# Board.net
KiCad netlist of a schematic drawn in EAGLE
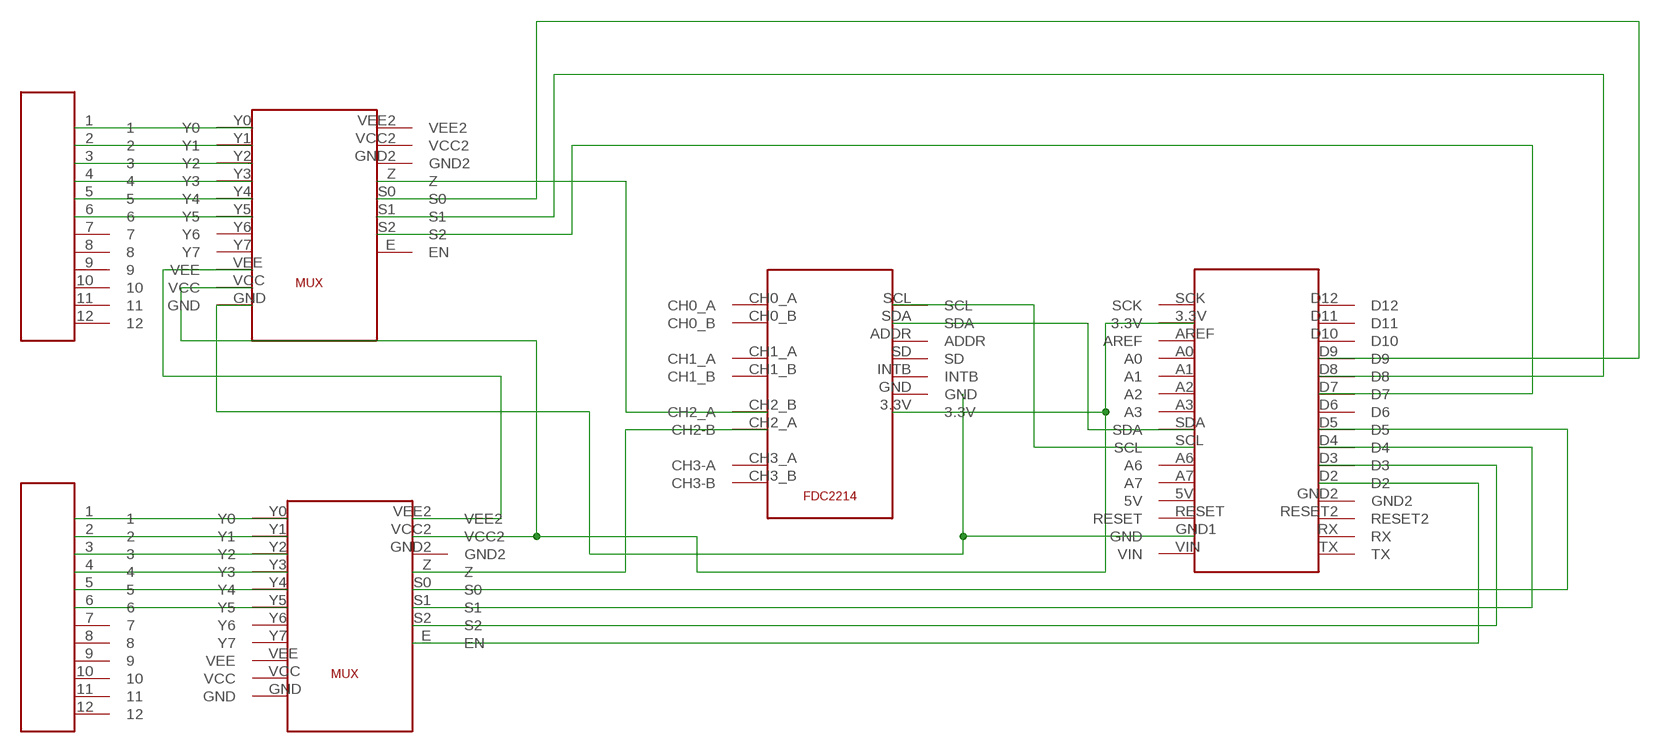
[diagram p0: schematic, sheet 1]

(export (version "E")
  (design (tool "Eeschema 10.0.6"))
  (components
    (comp (ref "U$1")
      (value "BLE33BLE33")
      (footprint "eagle-import:BLE33")
      (libsource (lib "eagle-import") (part "BLE33BLE33"))
    )
    (comp (ref "U$2")
      (value "MUXMUX")
      (footprint "eagle-import:MUX")
      (libsource (lib "eagle-import") (part "MUXMUX"))
    )
    (comp (ref "U$3")
      (value "MUXMUX")
      (footprint "eagle-import:MUX")
      (libsource (lib "eagle-import") (part "MUXMUX"))
    )
    (comp (ref "U$4")
      (value "MOLEXMOLEX")
      (footprint "eagle-import:MOLEX")
      (libsource (lib "eagle-import") (part "MOLEXMOLEX"))
    )
    (comp (ref "U$5")
      (value "MOLEXMOLEX")
      (footprint "eagle-import:MOLEX")
      (libsource (lib "eagle-import") (part "MOLEXMOLEX"))
    )
    (comp (ref "U$6")
      (value "FDC2214FDC2214")
      (footprint "eagle-import:FDC2214")
      (libsource (lib "eagle-import") (part "FDC2214FDC2214"))
    )
  )
  (nets
    (net (code "1") (name "Net-(U$1-GND)") (class "Default")
      (node (ref "U$1") (pin "GND1") (pinfunction "GND_GND1") (pintype "bidirectional"))
      (node (ref "U$2") (pin "GND") (pinfunction "GND_GND") (pintype "bidirectional"))
    )
    (net (code "2") (name "Net-(U$1-Pad3.3V)") (class "Default")
      (node (ref "U$1") (pin "3.3V") (pinfunction "3.3V_3.3V") (pintype "bidirectional"))
      (node (ref "U$2") (pin "VCC") (pinfunction "VCC_VCC") (pintype "bidirectional"))
      (node (ref "U$3") (pin "VCC2") (pinfunction "VCC2_VCC2") (pintype "bidirectional"))
      (node (ref "U$6") (pin "3.3V") (pinfunction "3.3V_3.3V") (pintype "bidirectional"))
    )
    (net (code "3") (name "Net-(U$1-PadD3)") (class "Default")
      (node (ref "U$1") (pin "D3") (pinfunction "D3_D3") (pintype "bidirectional"))
      (node (ref "U$3") (pin "S2") (pinfunction "S2_S2") (pintype "bidirectional"))
    )
    (net (code "4") (name "Net-(U$1-PadD4)") (class "Default")
      (node (ref "U$1") (pin "D4") (pinfunction "D4_D4") (pintype "bidirectional"))
      (node (ref "U$3") (pin "S1") (pinfunction "S1_S1") (pintype "bidirectional"))
    )
    (net (code "5") (name "Net-(U$1-PadD5)") (class "Default")
      (node (ref "U$1") (pin "D5") (pinfunction "D5_D5") (pintype "bidirectional"))
      (node (ref "U$3") (pin "S0") (pinfunction "S0_S0") (pintype "bidirectional"))
    )
    (net (code "6") (name "Net-(U$1-PadD7)") (class "Default")
      (node (ref "U$1") (pin "D7") (pinfunction "D7_D7") (pintype "bidirectional"))
      (node (ref "U$2") (pin "S2") (pinfunction "S2_S2") (pintype "bidirectional"))
    )
    (net (code "7") (name "Net-(U$1-PadD8)") (class "Default")
      (node (ref "U$1") (pin "D8") (pinfunction "D8_D8") (pintype "bidirectional"))
      (node (ref "U$2") (pin "S1") (pinfunction "S1_S1") (pintype "bidirectional"))
    )
    (net (code "8") (name "Net-(U$1-PadD9)") (class "Default")
      (node (ref "U$1") (pin "D9") (pinfunction "D9_D9") (pintype "bidirectional"))
      (node (ref "U$2") (pin "S0") (pinfunction "S0_S0") (pintype "bidirectional"))
    )
    (net (code "9") (name "Net-(U$1-PadSCL)") (class "Default")
      (node (ref "U$1") (pin "SCL") (pinfunction "SCL_SCL") (pintype "bidirectional"))
      (node (ref "U$6") (pin "SCL") (pinfunction "SCL_SCL") (pintype "bidirectional"))
    )
    (net (code "10") (name "Net-(U$1-PadSDA)") (class "Default")
      (node (ref "U$1") (pin "SDA") (pinfunction "SDA_SDA") (pintype "bidirectional"))
      (node (ref "U$6") (pin "SDA") (pinfunction "SDA_SDA") (pintype "bidirectional"))
    )
    (net (code "11") (name "Net-(U$2-PadVEE)") (class "Default")
      (node (ref "U$2") (pin "VEE") (pinfunction "VEE_VEE") (pintype "bidirectional"))
      (node (ref "U$3") (pin "VEE2") (pinfunction "VEE2_VEE2") (pintype "bidirectional"))
    )
    (net (code "12") (name "Net-(U$2-PadY0)") (class "Default")
      (node (ref "U$2") (pin "Y0") (pinfunction "Y0_Y0") (pintype "bidirectional"))
      (node (ref "U$4") (pin "1") (pinfunction "1_1") (pintype "bidirectional"))
    )
    (net (code "13") (name "Net-(U$2-PadY1)") (class "Default")
      (node (ref "U$2") (pin "Y1") (pinfunction "Y1_Y1") (pintype "bidirectional"))
      (node (ref "U$4") (pin "2") (pinfunction "2_2") (pintype "bidirectional"))
    )
    (net (code "14") (name "Net-(U$2-PadY2)") (class "Default")
      (node (ref "U$2") (pin "Y2") (pinfunction "Y2_Y2") (pintype "bidirectional"))
      (node (ref "U$4") (pin "3") (pinfunction "3_3") (pintype "bidirectional"))
    )
    (net (code "15") (name "Net-(U$2-PadY3)") (class "Default")
      (node (ref "U$2") (pin "Y3") (pinfunction "Y3_Y3") (pintype "bidirectional"))
      (node (ref "U$4") (pin "4") (pinfunction "4_4") (pintype "bidirectional"))
    )
    (net (code "16") (name "Net-(U$2-PadY4)") (class "Default")
      (node (ref "U$2") (pin "Y4") (pinfunction "Y4_Y4") (pintype "bidirectional"))
      (node (ref "U$4") (pin "5") (pinfunction "5_5") (pintype "bidirectional"))
    )
    (net (code "17") (name "Net-(U$2-PadY5)") (class "Default")
      (node (ref "U$2") (pin "Y5") (pinfunction "Y5_Y5") (pintype "bidirectional"))
      (node (ref "U$4") (pin "6") (pinfunction "6_6") (pintype "bidirectional"))
    )
    (net (code "18") (name "Net-(U$3-EN)") (class "Default")
      (node (ref "U$1") (pin "D2") (pinfunction "D2_D2") (pintype "bidirectional"))
      (node (ref "U$3") (pin "E") (pinfunction "EN_E") (pintype "bidirectional"))
    )
    (net (code "19") (name "Net-(U$3-PadY0)") (class "Default")
      (node (ref "U$3") (pin "Y0") (pinfunction "Y0_Y0") (pintype "bidirectional"))
      (node (ref "U$5") (pin "1") (pinfunction "1_1") (pintype "bidirectional"))
    )
    (net (code "20") (name "Net-(U$3-PadY1)") (class "Default")
      (node (ref "U$3") (pin "Y1") (pinfunction "Y1_Y1") (pintype "bidirectional"))
      (node (ref "U$5") (pin "2") (pinfunction "2_2") (pintype "bidirectional"))
    )
    (net (code "21") (name "Net-(U$3-PadY2)") (class "Default")
      (node (ref "U$3") (pin "Y2") (pinfunction "Y2_Y2") (pintype "bidirectional"))
      (node (ref "U$5") (pin "3") (pinfunction "3_3") (pintype "bidirectional"))
    )
    (net (code "22") (name "Net-(U$3-PadY3)") (class "Default")
      (node (ref "U$3") (pin "Y3") (pinfunction "Y3_Y3") (pintype "bidirectional"))
      (node (ref "U$5") (pin "4") (pinfunction "4_4") (pintype "bidirectional"))
    )
    (net (code "23") (name "Net-(U$3-PadY4)") (class "Default")
      (node (ref "U$3") (pin "Y4") (pinfunction "Y4_Y4") (pintype "bidirectional"))
      (node (ref "U$5") (pin "5") (pinfunction "5_5") (pintype "bidirectional"))
    )
    (net (code "24") (name "Net-(U$3-PadY5)") (class "Default")
      (node (ref "U$3") (pin "Y5") (pinfunction "Y5_Y5") (pintype "bidirectional"))
      (node (ref "U$5") (pin "6") (pinfunction "6_6") (pintype "bidirectional"))
    )
    (net (code "25") (name "Net-(U$6-CH2-B)") (class "Default")
      (node (ref "U$3") (pin "Z") (pinfunction "Z_Z") (pintype "bidirectional"))
      (node (ref "U$6") (pin "CH2_A") (pinfunction "CH2-B_CH2_A") (pintype "bidirectional"))
    )
    (net (code "26") (name "Net-(U$6-CH2_A)") (class "Default")
      (node (ref "U$2") (pin "Z") (pinfunction "Z_Z") (pintype "bidirectional"))
      (node (ref "U$6") (pin "CH2_B") (pinfunction "CH2_A_CH2_B") (pintype "bidirectional"))
    )
    (net (code "27") (name "unconnected-(U$1-Pad5V)") (class "Default")
      (node (ref "U$1") (pin "5V") (pinfunction "5V_5V") (pintype "bidirectional"))
    )
    (net (code "28") (name "unconnected-(U$1-PadA0)") (class "Default")
      (node (ref "U$1") (pin "A0") (pinfunction "A0_A0") (pintype "bidirectional"))
    )
    (net (code "29") (name "unconnected-(U$1-PadA1)") (class "Default")
      (node (ref "U$1") (pin "A1") (pinfunction "A1_A1") (pintype "bidirectional"))
    )
    (net (code "30") (name "unconnected-(U$1-PadA2)") (class "Default")
      (node (ref "U$1") (pin "A2") (pinfunction "A2_A2") (pintype "bidirectional"))
    )
    (net (code "31") (name "unconnected-(U$1-PadA3)") (class "Default")
      (node (ref "U$1") (pin "A3") (pinfunction "A3_A3") (pintype "bidirectional"))
    )
    (net (code "32") (name "unconnected-(U$1-PadA6)") (class "Default")
      (node (ref "U$1") (pin "A6") (pinfunction "A6_A6") (pintype "bidirectional"))
    )
    (net (code "33") (name "unconnected-(U$1-PadA7)") (class "Default")
      (node (ref "U$1") (pin "A7") (pinfunction "A7_A7") (pintype "bidirectional"))
    )
    (net (code "34") (name "unconnected-(U$1-PadAREF)") (class "Default")
      (node (ref "U$1") (pin "AREF") (pinfunction "AREF_AREF") (pintype "bidirectional"))
    )
    (net (code "35") (name "unconnected-(U$1-PadD6)") (class "Default")
      (node (ref "U$1") (pin "D6") (pinfunction "D6_D6") (pintype "bidirectional"))
    )
    (net (code "36") (name "unconnected-(U$1-PadD10)") (class "Default")
      (node (ref "U$1") (pin "D10") (pinfunction "D10_D10") (pintype "bidirectional"))
    )
    (net (code "37") (name "unconnected-(U$1-PadD11)") (class "Default")
      (node (ref "U$1") (pin "D11") (pinfunction "D11_D11") (pintype "bidirectional"))
    )
    (net (code "38") (name "unconnected-(U$1-PadD12)") (class "Default")
      (node (ref "U$1") (pin "D12") (pinfunction "D12_D12") (pintype "bidirectional"))
    )
    (net (code "39") (name "unconnected-(U$1-PadGND2)") (class "Default")
      (node (ref "U$1") (pin "GND2") (pinfunction "GND2_GND2") (pintype "bidirectional"))
    )
    (net (code "40") (name "unconnected-(U$1-PadRESET)") (class "Default")
      (node (ref "U$1") (pin "RESET") (pinfunction "RESET_RESET") (pintype "bidirectional"))
    )
    (net (code "41") (name "unconnected-(U$1-PadRESET2)") (class "Default")
      (node (ref "U$1") (pin "RESET2") (pinfunction "RESET2_RESET2") (pintype "bidirectional"))
    )
    (net (code "42") (name "unconnected-(U$1-PadRX)") (class "Default")
      (node (ref "U$1") (pin "RX") (pinfunction "RX_RX") (pintype "bidirectional"))
    )
    (net (code "43") (name "unconnected-(U$1-PadSCK)") (class "Default")
      (node (ref "U$1") (pin "SCK") (pinfunction "SCK_SCK") (pintype "bidirectional"))
    )
    (net (code "44") (name "unconnected-(U$1-PadTX)") (class "Default")
      (node (ref "U$1") (pin "TX") (pinfunction "TX_TX") (pintype "bidirectional"))
    )
    (net (code "45") (name "unconnected-(U$1-PadVIN)") (class "Default")
      (node (ref "U$1") (pin "VIN") (pinfunction "VIN_VIN") (pintype "bidirectional"))
    )
    (net (code "46") (name "unconnected-(U$2-EN-PadE)") (class "Default")
      (node (ref "U$2") (pin "E") (pinfunction "EN_E") (pintype "bidirectional"))
    )
    (net (code "47") (name "unconnected-(U$2-PadGND2)") (class "Default")
      (node (ref "U$2") (pin "GND2") (pinfunction "GND2_GND2") (pintype "bidirectional"))
    )
    (net (code "48") (name "unconnected-(U$2-PadVCC2)") (class "Default")
      (node (ref "U$2") (pin "VCC2") (pinfunction "VCC2_VCC2") (pintype "bidirectional"))
    )
    (net (code "49") (name "unconnected-(U$2-PadVEE2)") (class "Default")
      (node (ref "U$2") (pin "VEE2") (pinfunction "VEE2_VEE2") (pintype "bidirectional"))
    )
    (net (code "50") (name "unconnected-(U$2-PadY6)") (class "Default")
      (node (ref "U$2") (pin "Y6") (pinfunction "Y6_Y6") (pintype "bidirectional"))
    )
    (net (code "51") (name "unconnected-(U$2-PadY7)") (class "Default")
      (node (ref "U$2") (pin "Y7") (pinfunction "Y7_Y7") (pintype "bidirectional"))
    )
    (net (code "52") (name "unconnected-(U$3-PadGND)") (class "Default")
      (node (ref "U$3") (pin "GND") (pinfunction "GND_GND") (pintype "bidirectional"))
    )
    (net (code "53") (name "unconnected-(U$3-PadGND2)") (class "Default")
      (node (ref "U$3") (pin "GND2") (pinfunction "GND2_GND2") (pintype "bidirectional"))
    )
    (net (code "54") (name "unconnected-(U$3-PadVCC)") (class "Default")
      (node (ref "U$3") (pin "VCC") (pinfunction "VCC_VCC") (pintype "bidirectional"))
    )
    (net (code "55") (name "unconnected-(U$3-PadVEE)") (class "Default")
      (node (ref "U$3") (pin "VEE") (pinfunction "VEE_VEE") (pintype "bidirectional"))
    )
    (net (code "56") (name "unconnected-(U$3-PadY6)") (class "Default")
      (node (ref "U$3") (pin "Y6") (pinfunction "Y6_Y6") (pintype "bidirectional"))
    )
    (net (code "57") (name "unconnected-(U$3-PadY7)") (class "Default")
      (node (ref "U$3") (pin "Y7") (pinfunction "Y7_Y7") (pintype "bidirectional"))
    )
    (net (code "58") (name "unconnected-(U$4-Pad7)") (class "Default")
      (node (ref "U$4") (pin "7") (pinfunction "7_7") (pintype "bidirectional"))
    )
    (net (code "59") (name "unconnected-(U$4-Pad8)") (class "Default")
      (node (ref "U$4") (pin "8") (pinfunction "8_8") (pintype "bidirectional"))
    )
    (net (code "60") (name "unconnected-(U$4-Pad9)") (class "Default")
      (node (ref "U$4") (pin "9") (pinfunction "9_9") (pintype "bidirectional"))
    )
    (net (code "61") (name "unconnected-(U$4-Pad10)") (class "Default")
      (node (ref "U$4") (pin "10") (pinfunction "10_10") (pintype "bidirectional"))
    )
    (net (code "62") (name "unconnected-(U$4-Pad11)") (class "Default")
      (node (ref "U$4") (pin "11") (pinfunction "11_11") (pintype "bidirectional"))
    )
    (net (code "63") (name "unconnected-(U$4-Pad12)") (class "Default")
      (node (ref "U$4") (pin "12") (pinfunction "12_12") (pintype "bidirectional"))
    )
    (net (code "64") (name "unconnected-(U$5-Pad7)") (class "Default")
      (node (ref "U$5") (pin "7") (pinfunction "7_7") (pintype "bidirectional"))
    )
    (net (code "65") (name "unconnected-(U$5-Pad8)") (class "Default")
      (node (ref "U$5") (pin "8") (pinfunction "8_8") (pintype "bidirectional"))
    )
    (net (code "66") (name "unconnected-(U$5-Pad9)") (class "Default")
      (node (ref "U$5") (pin "9") (pinfunction "9_9") (pintype "bidirectional"))
    )
    (net (code "67") (name "unconnected-(U$5-Pad10)") (class "Default")
      (node (ref "U$5") (pin "10") (pinfunction "10_10") (pintype "bidirectional"))
    )
    (net (code "68") (name "unconnected-(U$5-Pad11)") (class "Default")
      (node (ref "U$5") (pin "11") (pinfunction "11_11") (pintype "bidirectional"))
    )
    (net (code "69") (name "unconnected-(U$5-Pad12)") (class "Default")
      (node (ref "U$5") (pin "12") (pinfunction "12_12") (pintype "bidirectional"))
    )
    (net (code "70") (name "unconnected-(U$6-CH3-A-PadCH3_A)") (class "Default")
      (node (ref "U$6") (pin "CH3_A") (pinfunction "CH3-A_CH3_A") (pintype "bidirectional"))
    )
    (net (code "71") (name "unconnected-(U$6-CH3-B-PadCH3_B)") (class "Default")
      (node (ref "U$6") (pin "CH3_B") (pinfunction "CH3-B_CH3_B") (pintype "bidirectional"))
    )
    (net (code "72") (name "unconnected-(U$6-PadADDR)") (class "Default")
      (node (ref "U$6") (pin "ADDR") (pinfunction "ADDR_ADDR") (pintype "bidirectional"))
    )
    (net (code "73") (name "unconnected-(U$6-PadCH0_A)") (class "Default")
      (node (ref "U$6") (pin "CH0_A") (pinfunction "CH0_A_CH0_A") (pintype "bidirectional"))
    )
    (net (code "74") (name "unconnected-(U$6-PadCH0_B)") (class "Default")
      (node (ref "U$6") (pin "CH0_B") (pinfunction "CH0_B_CH0_B") (pintype "bidirectional"))
    )
    (net (code "75") (name "unconnected-(U$6-PadCH1_A)") (class "Default")
      (node (ref "U$6") (pin "CH1_A") (pinfunction "CH1_A_CH1_A") (pintype "bidirectional"))
    )
    (net (code "76") (name "unconnected-(U$6-PadCH1_B)") (class "Default")
      (node (ref "U$6") (pin "CH1_B") (pinfunction "CH1_B_CH1_B") (pintype "bidirectional"))
    )
    (net (code "77") (name "unconnected-(U$6-PadGND)") (class "Default")
      (node (ref "U$6") (pin "GND") (pinfunction "GND_GND") (pintype "bidirectional"))
    )
    (net (code "78") (name "unconnected-(U$6-PadINTB)") (class "Default")
      (node (ref "U$6") (pin "INTB") (pinfunction "INTB_INTB") (pintype "bidirectional"))
    )
    (net (code "79") (name "unconnected-(U$6-PadSD)") (class "Default")
      (node (ref "U$6") (pin "SD") (pinfunction "SD_SD") (pintype "bidirectional"))
    )
  )
)
